# Sensores_2018.net
KiCad netlist of a schematic drawn in EAGLE
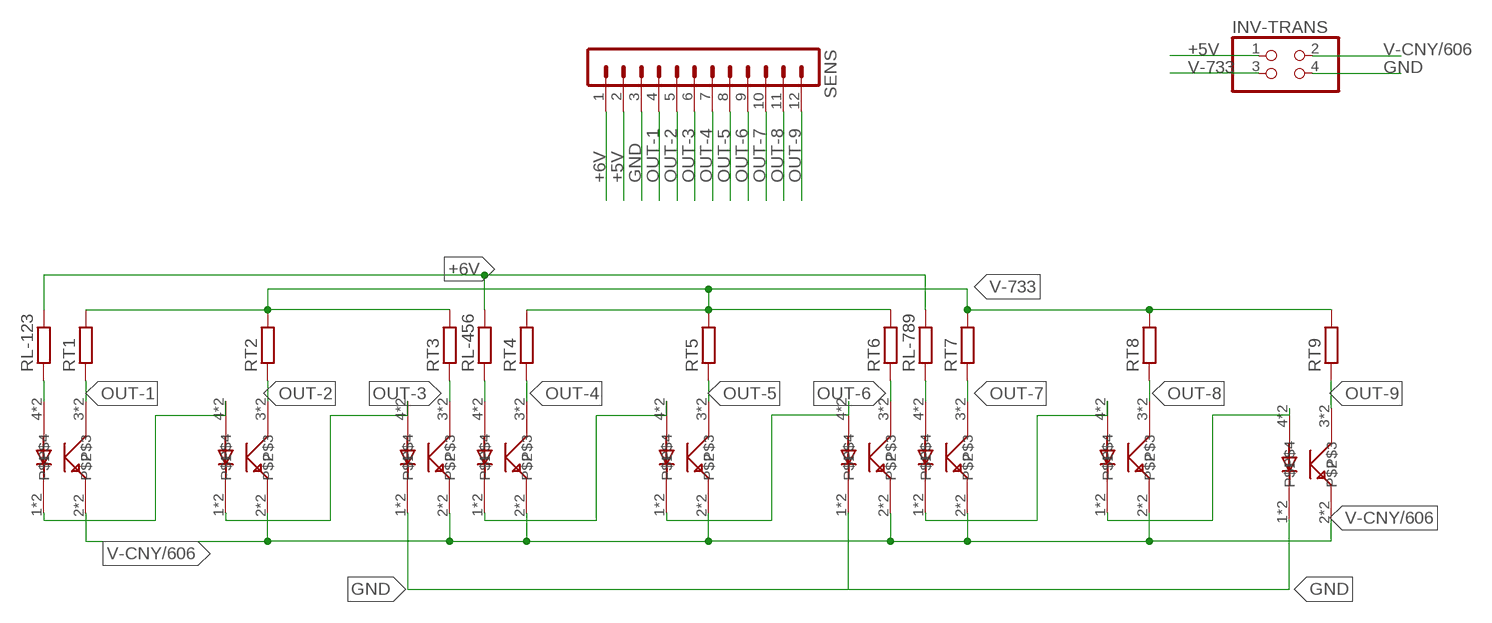
[diagram p0: schematic, sheet 1]

(export (version "E")
  (design (tool "Eeschema 10.0.6"))
  (components
    (comp (ref "INV-TRANS")
      (value "PINHD-2X2")
      (footprint "eagle-import:2X02")
      (libsource (lib "eagle-import") (part "PINHD-2X2"))
    )
    (comp (ref "RL-123")
      (value "R-EU_R0805W")
      (footprint "eagle-import:R0805W")
      (libsource (lib "eagle-import") (part "R-EU_R0805W"))
    )
    (comp (ref "RL-456")
      (value "R-EU_R0805W")
      (footprint "eagle-import:R0805W")
      (libsource (lib "eagle-import") (part "R-EU_R0805W"))
    )
    (comp (ref "RL-789")
      (value "R-EU_R0805W")
      (footprint "eagle-import:R0805W")
      (libsource (lib "eagle-import") (part "R-EU_R0805W"))
    )
    (comp (ref "RT1")
      (value "R-EU_R0805W")
      (footprint "eagle-import:R0805W")
      (libsource (lib "eagle-import") (part "R-EU_R0805W"))
    )
    (comp (ref "RT2")
      (value "R-EU_R0805W")
      (footprint "eagle-import:R0805W")
      (libsource (lib "eagle-import") (part "R-EU_R0805W"))
    )
    (comp (ref "RT3")
      (value "R-EU_R0805W")
      (footprint "eagle-import:R0805W")
      (libsource (lib "eagle-import") (part "R-EU_R0805W"))
    )
    (comp (ref "RT4")
      (value "R-EU_R0805W")
      (footprint "eagle-import:R0805W")
      (libsource (lib "eagle-import") (part "R-EU_R0805W"))
    )
    (comp (ref "RT5")
      (value "R-EU_R0805W")
      (footprint "eagle-import:R0805W")
      (libsource (lib "eagle-import") (part "R-EU_R0805W"))
    )
    (comp (ref "RT6")
      (value "R-EU_R0805W")
      (footprint "eagle-import:R0805W")
      (libsource (lib "eagle-import") (part "R-EU_R0805W"))
    )
    (comp (ref "RT7")
      (value "R-EU_R0805W")
      (footprint "eagle-import:R0805W")
      (libsource (lib "eagle-import") (part "R-EU_R0805W"))
    )
    (comp (ref "RT8")
      (value "R-EU_R0805W")
      (footprint "eagle-import:R0805W")
      (libsource (lib "eagle-import") (part "R-EU_R0805W"))
    )
    (comp (ref "RT9")
      (value "R-EU_R0805W")
      (footprint "eagle-import:R0805W")
      (libsource (lib "eagle-import") (part "R-EU_R0805W"))
    )
    (comp (ref "S1")
      (value "OPB733+OPB606+CNY70")
      (footprint "eagle-import:OPB733+606")
      (libsource (lib "eagle-import") (part "OPB733+OPB606+CNY70"))
    )
    (comp (ref "S2")
      (value "OPB733+OPB606+CNY70")
      (footprint "eagle-import:OPB733+606")
      (libsource (lib "eagle-import") (part "OPB733+OPB606+CNY70"))
    )
    (comp (ref "S3")
      (value "OPB733+OPB606+CNY70")
      (footprint "eagle-import:OPB733+606")
      (libsource (lib "eagle-import") (part "OPB733+OPB606+CNY70"))
    )
    (comp (ref "S4")
      (value "OPB733+OPB606+CNY70")
      (footprint "eagle-import:OPB733+606")
      (libsource (lib "eagle-import") (part "OPB733+OPB606+CNY70"))
    )
    (comp (ref "S5")
      (value "OPB733+OPB606+CNY70")
      (footprint "eagle-import:OPB733+606")
      (libsource (lib "eagle-import") (part "OPB733+OPB606+CNY70"))
    )
    (comp (ref "S6")
      (value "OPB733+OPB606+CNY70")
      (footprint "eagle-import:OPB733+606")
      (libsource (lib "eagle-import") (part "OPB733+OPB606+CNY70"))
    )
    (comp (ref "S7")
      (value "OPB733+OPB606+CNY70")
      (footprint "eagle-import:OPB733+606")
      (libsource (lib "eagle-import") (part "OPB733+OPB606+CNY70"))
    )
    (comp (ref "S8")
      (value "OPB733+OPB606+CNY70")
      (footprint "eagle-import:OPB733+606")
      (libsource (lib "eagle-import") (part "OPB733+OPB606+CNY70"))
    )
    (comp (ref "S9")
      (value "OPB733+OPB606+CNY70")
      (footprint "eagle-import:OPB733+606")
      (libsource (lib "eagle-import") (part "OPB733+OPB606+CNY70"))
    )
    (comp (ref "SENS")
      (value "MA12-1")
      (footprint "eagle-import:MA12-1")
      (fields (field (name "SPICEPREFIX") "X"))
      (libsource (lib "eagle-import") (part "MA12-1"))
    )
  )
  (nets
    (net (code "1") (name "+6V") (class "Default")
      (node (ref "RL-123") (pin "2") (pinfunction "2_2") (pintype "passive"))
      (node (ref "RL-456") (pin "2") (pinfunction "2_2") (pintype "passive"))
      (node (ref "RL-789") (pin "2") (pinfunction "2_2") (pintype "passive"))
      (node (ref "SENS") (pin "1") (pinfunction "1_1") (pintype "passive"))
    )
    (net (code "2") (name "/+5V") (class "Default")
      (node (ref "INV-TRANS") (pin "1") (pinfunction "1_1") (pintype "passive"))
      (node (ref "SENS") (pin "2") (pinfunction "2_2") (pintype "passive"))
    )
    (net (code "3") (name "GND") (class "Default")
      (node (ref "INV-TRANS") (pin "4") (pinfunction "4_4") (pintype "passive"))
      (node (ref "S3") (pin "1") (pinfunction "P$4_1") (pintype "bidirectional"))
      (node (ref "S3") (pin "P$1") (pinfunction "P$4_P$1") (pintype "bidirectional"))
      (node (ref "S6") (pin "1") (pinfunction "P$4_1") (pintype "bidirectional"))
      (node (ref "S6") (pin "P$1") (pinfunction "P$4_P$1") (pintype "bidirectional"))
      (node (ref "S9") (pin "1") (pinfunction "P$4_1") (pintype "bidirectional"))
      (node (ref "S9") (pin "P$1") (pinfunction "P$4_P$1") (pintype "bidirectional"))
      (node (ref "SENS") (pin "3") (pinfunction "3_3") (pintype "passive"))
    )
    (net (code "4") (name "Net-(RL-123-Pad1)") (class "Default")
      (node (ref "RL-123") (pin "1") (pinfunction "1_1") (pintype "passive"))
      (node (ref "S1") (pin "4") (pinfunction "P$1_4") (pintype "bidirectional"))
      (node (ref "S1") (pin "P$4") (pinfunction "P$1_P$4") (pintype "bidirectional"))
    )
    (net (code "5") (name "Net-(RL-456-Pad1)") (class "Default")
      (node (ref "RL-456") (pin "1") (pinfunction "1_1") (pintype "passive"))
      (node (ref "S4") (pin "4") (pinfunction "P$1_4") (pintype "bidirectional"))
      (node (ref "S4") (pin "P$4") (pinfunction "P$1_P$4") (pintype "bidirectional"))
    )
    (net (code "6") (name "Net-(RL-789-Pad1)") (class "Default")
      (node (ref "RL-789") (pin "1") (pinfunction "1_1") (pintype "passive"))
      (node (ref "S7") (pin "4") (pinfunction "P$1_4") (pintype "bidirectional"))
      (node (ref "S7") (pin "P$4") (pinfunction "P$1_P$4") (pintype "bidirectional"))
    )
    (net (code "7") (name "Net-(S1-P$4-Pad1)") (class "Default")
      (node (ref "S1") (pin "1") (pinfunction "P$4_1") (pintype "bidirectional"))
      (node (ref "S1") (pin "P$1") (pinfunction "P$4_P$1") (pintype "bidirectional"))
      (node (ref "S2") (pin "4") (pinfunction "P$1_4") (pintype "bidirectional"))
      (node (ref "S2") (pin "P$4") (pinfunction "P$1_P$4") (pintype "bidirectional"))
    )
    (net (code "8") (name "Net-(S2-P$4-Pad1)") (class "Default")
      (node (ref "S2") (pin "1") (pinfunction "P$4_1") (pintype "bidirectional"))
      (node (ref "S2") (pin "P$1") (pinfunction "P$4_P$1") (pintype "bidirectional"))
      (node (ref "S3") (pin "4") (pinfunction "P$1_4") (pintype "bidirectional"))
      (node (ref "S3") (pin "P$4") (pinfunction "P$1_P$4") (pintype "bidirectional"))
    )
    (net (code "9") (name "Net-(S4-P$4-Pad1)") (class "Default")
      (node (ref "S4") (pin "1") (pinfunction "P$4_1") (pintype "bidirectional"))
      (node (ref "S4") (pin "P$1") (pinfunction "P$4_P$1") (pintype "bidirectional"))
      (node (ref "S5") (pin "4") (pinfunction "P$1_4") (pintype "bidirectional"))
      (node (ref "S5") (pin "P$4") (pinfunction "P$1_P$4") (pintype "bidirectional"))
    )
    (net (code "10") (name "Net-(S5-P$4-Pad1)") (class "Default")
      (node (ref "S5") (pin "1") (pinfunction "P$4_1") (pintype "bidirectional"))
      (node (ref "S5") (pin "P$1") (pinfunction "P$4_P$1") (pintype "bidirectional"))
      (node (ref "S6") (pin "4") (pinfunction "P$1_4") (pintype "bidirectional"))
      (node (ref "S6") (pin "P$4") (pinfunction "P$1_P$4") (pintype "bidirectional"))
    )
    (net (code "11") (name "Net-(S7-P$4-Pad1)") (class "Default")
      (node (ref "S7") (pin "1") (pinfunction "P$4_1") (pintype "bidirectional"))
      (node (ref "S7") (pin "P$1") (pinfunction "P$4_P$1") (pintype "bidirectional"))
      (node (ref "S8") (pin "4") (pinfunction "P$1_4") (pintype "bidirectional"))
      (node (ref "S8") (pin "P$4") (pinfunction "P$1_P$4") (pintype "bidirectional"))
    )
    (net (code "12") (name "Net-(S8-P$4-Pad1)") (class "Default")
      (node (ref "S8") (pin "1") (pinfunction "P$4_1") (pintype "bidirectional"))
      (node (ref "S8") (pin "P$1") (pinfunction "P$4_P$1") (pintype "bidirectional"))
      (node (ref "S9") (pin "4") (pinfunction "P$1_4") (pintype "bidirectional"))
      (node (ref "S9") (pin "P$4") (pinfunction "P$1_P$4") (pintype "bidirectional"))
    )
    (net (code "13") (name "OUT-1") (class "Default")
      (node (ref "RT1") (pin "1") (pinfunction "1_1") (pintype "passive"))
      (node (ref "S1") (pin "3") (pinfunction "P$2_3") (pintype "bidirectional"))
      (node (ref "S1") (pin "P$3") (pinfunction "P$2_P$3") (pintype "bidirectional"))
      (node (ref "SENS") (pin "4") (pinfunction "4_4") (pintype "passive"))
    )
    (net (code "14") (name "OUT-2") (class "Default")
      (node (ref "RT2") (pin "1") (pinfunction "1_1") (pintype "passive"))
      (node (ref "S2") (pin "3") (pinfunction "P$2_3") (pintype "bidirectional"))
      (node (ref "S2") (pin "P$3") (pinfunction "P$2_P$3") (pintype "bidirectional"))
      (node (ref "SENS") (pin "5") (pinfunction "5_5") (pintype "passive"))
    )
    (net (code "15") (name "OUT-3") (class "Default")
      (node (ref "RT3") (pin "1") (pinfunction "1_1") (pintype "passive"))
      (node (ref "S3") (pin "3") (pinfunction "P$2_3") (pintype "bidirectional"))
      (node (ref "S3") (pin "P$3") (pinfunction "P$2_P$3") (pintype "bidirectional"))
      (node (ref "SENS") (pin "6") (pinfunction "6_6") (pintype "passive"))
    )
    (net (code "16") (name "OUT-4") (class "Default")
      (node (ref "RT4") (pin "1") (pinfunction "1_1") (pintype "passive"))
      (node (ref "S4") (pin "3") (pinfunction "P$2_3") (pintype "bidirectional"))
      (node (ref "S4") (pin "P$3") (pinfunction "P$2_P$3") (pintype "bidirectional"))
      (node (ref "SENS") (pin "7") (pinfunction "7_7") (pintype "passive"))
    )
    (net (code "17") (name "OUT-5") (class "Default")
      (node (ref "RT5") (pin "1") (pinfunction "1_1") (pintype "passive"))
      (node (ref "S5") (pin "3") (pinfunction "P$2_3") (pintype "bidirectional"))
      (node (ref "S5") (pin "P$3") (pinfunction "P$2_P$3") (pintype "bidirectional"))
      (node (ref "SENS") (pin "8") (pinfunction "8_8") (pintype "passive"))
    )
    (net (code "18") (name "OUT-6") (class "Default")
      (node (ref "RT6") (pin "1") (pinfunction "1_1") (pintype "passive"))
      (node (ref "S6") (pin "3") (pinfunction "P$2_3") (pintype "bidirectional"))
      (node (ref "S6") (pin "P$3") (pinfunction "P$2_P$3") (pintype "bidirectional"))
      (node (ref "SENS") (pin "9") (pinfunction "9_9") (pintype "passive"))
    )
    (net (code "19") (name "OUT-7") (class "Default")
      (node (ref "RT7") (pin "1") (pinfunction "1_1") (pintype "passive"))
      (node (ref "S7") (pin "3") (pinfunction "P$2_3") (pintype "bidirectional"))
      (node (ref "S7") (pin "P$3") (pinfunction "P$2_P$3") (pintype "bidirectional"))
      (node (ref "SENS") (pin "10") (pinfunction "10_10") (pintype "passive"))
    )
    (net (code "20") (name "OUT-8") (class "Default")
      (node (ref "RT8") (pin "1") (pinfunction "1_1") (pintype "passive"))
      (node (ref "S8") (pin "3") (pinfunction "P$2_3") (pintype "bidirectional"))
      (node (ref "S8") (pin "P$3") (pinfunction "P$2_P$3") (pintype "bidirectional"))
      (node (ref "SENS") (pin "11") (pinfunction "11_11") (pintype "passive"))
    )
    (net (code "21") (name "OUT-9") (class "Default")
      (node (ref "RT9") (pin "1") (pinfunction "1_1") (pintype "passive"))
      (node (ref "S9") (pin "3") (pinfunction "P$2_3") (pintype "bidirectional"))
      (node (ref "S9") (pin "P$3") (pinfunction "P$2_P$3") (pintype "bidirectional"))
      (node (ref "SENS") (pin "12") (pinfunction "12_12") (pintype "passive"))
    )
    (net (code "22") (name "V-733") (class "Default")
      (node (ref "INV-TRANS") (pin "3") (pinfunction "3_3") (pintype "passive"))
      (node (ref "RT1") (pin "2") (pinfunction "2_2") (pintype "passive"))
      (node (ref "RT2") (pin "2") (pinfunction "2_2") (pintype "passive"))
      (node (ref "RT3") (pin "2") (pinfunction "2_2") (pintype "passive"))
      (node (ref "RT4") (pin "2") (pinfunction "2_2") (pintype "passive"))
      (node (ref "RT5") (pin "2") (pinfunction "2_2") (pintype "passive"))
      (node (ref "RT6") (pin "2") (pinfunction "2_2") (pintype "passive"))
      (node (ref "RT7") (pin "2") (pinfunction "2_2") (pintype "passive"))
      (node (ref "RT8") (pin "2") (pinfunction "2_2") (pintype "passive"))
      (node (ref "RT9") (pin "2") (pinfunction "2_2") (pintype "passive"))
    )
    (net (code "23") (name "V-CNY{slash}606") (class "Default")
      (node (ref "INV-TRANS") (pin "2") (pinfunction "2_2") (pintype "passive"))
      (node (ref "S1") (pin "2") (pinfunction "P$3_2") (pintype "bidirectional"))
      (node (ref "S1") (pin "P$2") (pinfunction "P$3_P$2") (pintype "bidirectional"))
      (node (ref "S2") (pin "2") (pinfunction "P$3_2") (pintype "bidirectional"))
      (node (ref "S2") (pin "P$2") (pinfunction "P$3_P$2") (pintype "bidirectional"))
      (node (ref "S3") (pin "2") (pinfunction "P$3_2") (pintype "bidirectional"))
      (node (ref "S3") (pin "P$2") (pinfunction "P$3_P$2") (pintype "bidirectional"))
      (node (ref "S4") (pin "2") (pinfunction "P$3_2") (pintype "bidirectional"))
      (node (ref "S4") (pin "P$2") (pinfunction "P$3_P$2") (pintype "bidirectional"))
      (node (ref "S5") (pin "2") (pinfunction "P$3_2") (pintype "bidirectional"))
      (node (ref "S5") (pin "P$2") (pinfunction "P$3_P$2") (pintype "bidirectional"))
      (node (ref "S6") (pin "2") (pinfunction "P$3_2") (pintype "bidirectional"))
      (node (ref "S6") (pin "P$2") (pinfunction "P$3_P$2") (pintype "bidirectional"))
      (node (ref "S7") (pin "2") (pinfunction "P$3_2") (pintype "bidirectional"))
      (node (ref "S7") (pin "P$2") (pinfunction "P$3_P$2") (pintype "bidirectional"))
      (node (ref "S8") (pin "2") (pinfunction "P$3_2") (pintype "bidirectional"))
      (node (ref "S8") (pin "P$2") (pinfunction "P$3_P$2") (pintype "bidirectional"))
      (node (ref "S9") (pin "2") (pinfunction "P$3_2") (pintype "bidirectional"))
      (node (ref "S9") (pin "P$2") (pinfunction "P$3_P$2") (pintype "bidirectional"))
    )
  )
)
